# freq_ik3oil.net
KiCad netlist of a schematic drawn in EAGLE
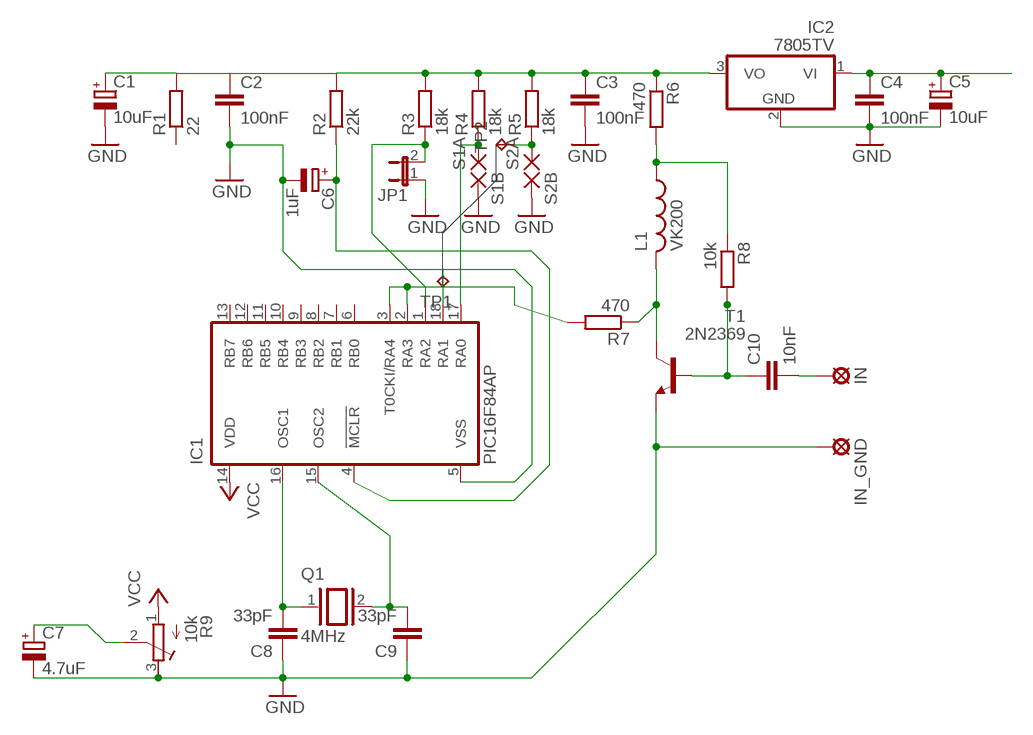
[diagram p0: schematic, sheet 1]

(export (version "E")
  (design (tool "Eeschema 10.0.6"))
  (components
    (comp (ref "C1")
      (value "10uF")
      (footprint "eagle-import:E2,5-7")
      (libsource (lib "eagle-import") (part "CPOL-EUE2.5-7"))
    )
    (comp (ref "C2")
      (value "100nF")
      (footprint "eagle-import:C050-024X044")
      (libsource (lib "eagle-import") (part "C-EU050-024X044"))
    )
    (comp (ref "C3")
      (value "100nF")
      (footprint "eagle-import:C050-024X044")
      (libsource (lib "eagle-import") (part "C-EU050-024X044"))
    )
    (comp (ref "C4")
      (value "100nF")
      (footprint "eagle-import:C050-024X044")
      (libsource (lib "eagle-import") (part "C-EU050-024X044"))
    )
    (comp (ref "C5")
      (value "10uF")
      (footprint "eagle-import:E2,5-7")
      (libsource (lib "eagle-import") (part "CPOL-EUE2.5-7"))
    )
    (comp (ref "C6")
      (value "1uF")
      (footprint "eagle-import:E2,5-7")
      (libsource (lib "eagle-import") (part "CPOL-EUE2.5-7"))
    )
    (comp (ref "C7")
      (value "4.7uF")
      (footprint "eagle-import:E2,5-7")
      (libsource (lib "eagle-import") (part "CPOL-EUE2.5-7"))
    )
    (comp (ref "C8")
      (value "33pF")
      (footprint "eagle-import:C050-024X044")
      (libsource (lib "eagle-import") (part "C-EU050-024X044"))
    )
    (comp (ref "C9")
      (value "33pF")
      (footprint "eagle-import:C050-024X044")
      (libsource (lib "eagle-import") (part "C-EU050-024X044"))
    )
    (comp (ref "C10")
      (value "10nF")
      (footprint "eagle-import:C050-024X044")
      (libsource (lib "eagle-import") (part "C-EU050-024X044"))
    )
    (comp (ref "IC1")
      (value "PIC16F84AP")
      (footprint "eagle-import:DIL18")
      (libsource (lib "eagle-import") (part "PIC16F8P4A"))
    )
    (comp (ref "IC2")
      (value "7805TV")
      (footprint "eagle-import:TO220V")
      (libsource (lib "eagle-import") (part "78TV05"))
    )
    (comp (ref "IN")
      (value "LSP10")
      (footprint "eagle-import:LSP10")
      (libsource (lib "eagle-import") (part "LSP10"))
    )
    (comp (ref "IN_GND")
      (value "LSP10")
      (footprint "eagle-import:LSP10")
      (libsource (lib "eagle-import") (part "LSP10"))
    )
    (comp (ref "JP1")
      (value "JP1E")
      (footprint "eagle-import:JP1")
      (libsource (lib "eagle-import") (part "JP1E"))
    )
    (comp (ref "L1")
      (value "VK200")
      (footprint "eagle-import:TFI0307")
      (libsource (lib "eagle-import") (part "L-USTFI0307"))
    )
    (comp (ref "Q1")
      (value "4MHz")
      (footprint "eagle-import:QS")
      (libsource (lib "eagle-import") (part "XTAL/S"))
    )
    (comp (ref "R1")
      (value "22")
      (footprint "eagle-import:0204_7")
      (libsource (lib "eagle-import") (part "R-EU_0204/7"))
    )
    (comp (ref "R2")
      (value "22k")
      (footprint "eagle-import:0204_7")
      (libsource (lib "eagle-import") (part "R-EU_0204/7"))
    )
    (comp (ref "R3")
      (value "18k")
      (footprint "eagle-import:0204_7")
      (libsource (lib "eagle-import") (part "R-EU_0204/7"))
    )
    (comp (ref "R4")
      (value "18k")
      (footprint "eagle-import:0204_7")
      (libsource (lib "eagle-import") (part "R-EU_0204/7"))
    )
    (comp (ref "R5")
      (value "18k")
      (footprint "eagle-import:0204_7")
      (libsource (lib "eagle-import") (part "R-EU_0204/7"))
    )
    (comp (ref "R6")
      (value "470")
      (footprint "eagle-import:0204_7")
      (libsource (lib "eagle-import") (part "R-EU_0204/7"))
    )
    (comp (ref "R7")
      (value "470")
      (footprint "eagle-import:0204_7")
      (libsource (lib "eagle-import") (part "R-EU_0204/7"))
    )
    (comp (ref "R8")
      (value "10k")
      (footprint "eagle-import:0204_7")
      (libsource (lib "eagle-import") (part "R-EU_0204/7"))
    )
    (comp (ref "R9")
      (value "10k")
      (footprint "eagle-import:RTRIM3339P")
      (libsource (lib "eagle-import") (part "R-TRIMM3339P"))
    )
    (comp (ref "S1A")
      (value "1,6/0,8")
      (footprint "eagle-import:1,6_0,8")
      (libsource (lib "eagle-import") (part "1,6/0,8"))
    )
    (comp (ref "S1B")
      (value "1,6/0,8")
      (footprint "eagle-import:1,6_0,8")
      (libsource (lib "eagle-import") (part "1,6/0,8"))
    )
    (comp (ref "S2A")
      (value "1,6/0,8")
      (footprint "eagle-import:1,6_0,8")
      (libsource (lib "eagle-import") (part "1,6/0,8"))
    )
    (comp (ref "S2B")
      (value "1,6/0,8")
      (footprint "eagle-import:1,6_0,8")
      (libsource (lib "eagle-import") (part "1,6/0,8"))
    )
    (comp (ref "T1")
      (value "2N2369")
      (footprint "eagle-import:TO18")
      (libsource (lib "eagle-import") (part "2N2369"))
    )
    (comp (ref "TP1")
      (value "TPB1,27")
      (footprint "eagle-import:B1,27")
      (libsource (lib "eagle-import") (part "TPB1,27"))
    )
    (comp (ref "TP2")
      (value "TPB1,27")
      (footprint "eagle-import:B1,27")
      (libsource (lib "eagle-import") (part "TPB1,27"))
    )
  )
  (nets
    (net (code "1") (name "GND") (class "Default")
      (node (ref "C1") (pin "-") (pinfunction "-_-") (pintype "passive"))
      (node (ref "C2") (pin "2") (pinfunction "2_2") (pintype "passive"))
      (node (ref "C3") (pin "2") (pinfunction "2_2") (pintype "passive"))
      (node (ref "C4") (pin "2") (pinfunction "2_2") (pintype "passive"))
      (node (ref "C5") (pin "-") (pinfunction "-_-") (pintype "passive"))
      (node (ref "C6") (pin "-") (pinfunction "-_-") (pintype "passive"))
      (node (ref "C7") (pin "-") (pinfunction "-_-") (pintype "passive"))
      (node (ref "C8") (pin "1") (pinfunction "1_1") (pintype "passive"))
      (node (ref "C9") (pin "1") (pinfunction "1_1") (pintype "passive"))
      (node (ref "IC1") (pin "5") (pinfunction "VSS_5") (pintype "power_in"))
      (node (ref "IC2") (pin "2") (pinfunction "GND_2") (pintype "passive"))
      (node (ref "IN_GND") (pin "MP") (pinfunction "MP_MP") (pintype "passive"))
      (node (ref "JP1") (pin "1") (pinfunction "1_1") (pintype "passive"))
      (node (ref "R9") (pin "3") (pinfunction "E_3") (pintype "passive"))
      (node (ref "S1B") (pin "1") (pinfunction "P_1") (pintype "passive"))
      (node (ref "S2B") (pin "1") (pinfunction "P_1") (pintype "passive"))
      (node (ref "T1") (pin "1") (pinfunction "E_1") (pintype "passive"))
    )
    (net (code "2") (name "Net-(C10-Pad2)") (class "Default")
      (node (ref "C10") (pin "2") (pinfunction "2_2") (pintype "passive"))
      (node (ref "IN") (pin "MP") (pinfunction "MP_MP") (pintype "passive"))
    )
    (net (code "3") (name "Net-(IC1-OSC1)") (class "Default")
      (node (ref "C8") (pin "2") (pinfunction "2_2") (pintype "passive"))
      (node (ref "IC1") (pin "16") (pinfunction "OSC1_16") (pintype "input"))
      (node (ref "Q1") (pin "1") (pinfunction "1_1") (pintype "passive"))
    )
    (net (code "4") (name "Net-(IC1-OSC2)") (class "Default")
      (node (ref "C9") (pin "2") (pinfunction "2_2") (pintype "passive"))
      (node (ref "IC1") (pin "15") (pinfunction "OSC2_15") (pintype "output"))
      (node (ref "Q1") (pin "2") (pinfunction "2_2") (pintype "passive"))
    )
    (net (code "5") (name "Net-(IC1-RA0)") (class "Default")
      (node (ref "IC1") (pin "17") (pinfunction "RA0_17") (pintype "bidirectional"))
      (node (ref "R4") (pin "1") (pinfunction "1_1") (pintype "passive"))
      (node (ref "S1A") (pin "1") (pinfunction "P_1") (pintype "passive"))
    )
    (net (code "6") (name "Net-(IC1-RA1)") (class "Default")
      (node (ref "IC1") (pin "18") (pinfunction "RA1_18") (pintype "bidirectional"))
      (node (ref "TP1") (pin "TP") (pinfunction "TP_TP") (pintype "input"))
    )
    (net (code "7") (name "Net-(IC1-RA2)") (class "Default")
      (node (ref "IC1") (pin "1") (pinfunction "RA2_1") (pintype "bidirectional"))
      (node (ref "JP1") (pin "2") (pinfunction "2_2") (pintype "passive"))
      (node (ref "R3") (pin "1") (pinfunction "1_1") (pintype "passive"))
    )
    (net (code "8") (name "Net-(IC1-RA3)") (class "Default")
      (node (ref "IC1") (pin "2") (pinfunction "RA3_2") (pintype "bidirectional"))
      (node (ref "IC1") (pin "3") (pinfunction "T0CKI/RA4_3") (pintype "bidirectional"))
      (node (ref "R7") (pin "2") (pinfunction "2_2") (pintype "passive"))
    )
    (net (code "9") (name "Net-(IC1-~{MCLR})") (class "Default")
      (node (ref "C6") (pin "+") (pinfunction "+_+") (pintype "passive"))
      (node (ref "IC1") (pin "4") (pinfunction "~{MCLR}_4") (pintype "input"))
      (node (ref "R2") (pin "1") (pinfunction "1_1") (pintype "passive"))
    )
    (net (code "10") (name "Net-(IC2-VI)") (class "Default")
      (node (ref "C4") (pin "1") (pinfunction "1_1") (pintype "passive"))
      (node (ref "C5") (pin "+") (pinfunction "+_+") (pintype "passive"))
      (node (ref "IC2") (pin "1") (pinfunction "VI_1") (pintype "input"))
    )
    (net (code "11") (name "Net-(IC2-VO)") (class "Default")
      (node (ref "C1") (pin "+") (pinfunction "+_+") (pintype "passive"))
      (node (ref "C2") (pin "1") (pinfunction "1_1") (pintype "passive"))
      (node (ref "C3") (pin "1") (pinfunction "1_1") (pintype "passive"))
      (node (ref "IC2") (pin "3") (pinfunction "VO_3") (pintype "passive"))
      (node (ref "R1") (pin "2") (pinfunction "2_2") (pintype "passive"))
      (node (ref "R2") (pin "2") (pinfunction "2_2") (pintype "passive"))
      (node (ref "R3") (pin "2") (pinfunction "2_2") (pintype "passive"))
      (node (ref "R4") (pin "2") (pinfunction "2_2") (pintype "passive"))
      (node (ref "R5") (pin "2") (pinfunction "2_2") (pintype "passive"))
      (node (ref "R6") (pin "1") (pinfunction "1_1") (pintype "passive"))
    )
    (net (code "12") (name "Net-(L1-Pad1)") (class "Default")
      (node (ref "L1") (pin "1") (pinfunction "1_1") (pintype "passive"))
      (node (ref "R6") (pin "2") (pinfunction "2_2") (pintype "passive"))
      (node (ref "R8") (pin "1") (pinfunction "1_1") (pintype "passive"))
    )
    (net (code "13") (name "Net-(R9-S)") (class "Default")
      (node (ref "C7") (pin "+") (pinfunction "+_+") (pintype "passive"))
      (node (ref "R9") (pin "2") (pinfunction "S_2") (pintype "passive"))
    )
    (net (code "14") (name "Net-(S2A-P)") (class "Default")
      (node (ref "R5") (pin "1") (pinfunction "1_1") (pintype "passive"))
      (node (ref "S2A") (pin "1") (pinfunction "P_1") (pintype "passive"))
      (node (ref "TP2") (pin "TP") (pinfunction "TP_TP") (pintype "input"))
    )
    (net (code "15") (name "Net-(T1-B)") (class "Default")
      (node (ref "C10") (pin "1") (pinfunction "1_1") (pintype "passive"))
      (node (ref "R8") (pin "2") (pinfunction "2_2") (pintype "passive"))
      (node (ref "T1") (pin "2") (pinfunction "B_2") (pintype "passive"))
    )
    (net (code "16") (name "Net-(T1-C)") (class "Default")
      (node (ref "L1") (pin "2") (pinfunction "2_2") (pintype "passive"))
      (node (ref "R7") (pin "1") (pinfunction "1_1") (pintype "passive"))
      (node (ref "T1") (pin "3") (pinfunction "C_3") (pintype "passive"))
    )
    (net (code "17") (name "VCC") (class "Default")
      (node (ref "IC1") (pin "14") (pinfunction "VDD_14") (pintype "power_in"))
      (node (ref "R9") (pin "1") (pinfunction "A_1") (pintype "passive"))
    )
    (net (code "18") (name "unconnected-(IC1-RB0-Pad6)") (class "Default")
      (node (ref "IC1") (pin "6") (pinfunction "RB0_6") (pintype "bidirectional"))
    )
    (net (code "19") (name "unconnected-(IC1-RB1-Pad7)") (class "Default")
      (node (ref "IC1") (pin "7") (pinfunction "RB1_7") (pintype "bidirectional"))
    )
    (net (code "20") (name "unconnected-(IC1-RB2-Pad8)") (class "Default")
      (node (ref "IC1") (pin "8") (pinfunction "RB2_8") (pintype "bidirectional"))
    )
    (net (code "21") (name "unconnected-(IC1-RB3-Pad9)") (class "Default")
      (node (ref "IC1") (pin "9") (pinfunction "RB3_9") (pintype "bidirectional"))
    )
    (net (code "22") (name "unconnected-(IC1-RB4-Pad10)") (class "Default")
      (node (ref "IC1") (pin "10") (pinfunction "RB4_10") (pintype "bidirectional"))
    )
    (net (code "23") (name "unconnected-(IC1-RB5-Pad11)") (class "Default")
      (node (ref "IC1") (pin "11") (pinfunction "RB5_11") (pintype "bidirectional"))
    )
    (net (code "24") (name "unconnected-(IC1-RB6-Pad12)") (class "Default")
      (node (ref "IC1") (pin "12") (pinfunction "RB6_12") (pintype "bidirectional"))
    )
    (net (code "25") (name "unconnected-(IC1-RB7-Pad13)") (class "Default")
      (node (ref "IC1") (pin "13") (pinfunction "RB7_13") (pintype "bidirectional"))
    )
    (net (code "26") (name "unconnected-(R1-Pad1)") (class "Default")
      (node (ref "R1") (pin "1") (pinfunction "1_1") (pintype "passive"))
    )
  )
)
